# SparkFun_GPS_NEO_M9N.net
KiCad netlist of a schematic drawn in EAGLE
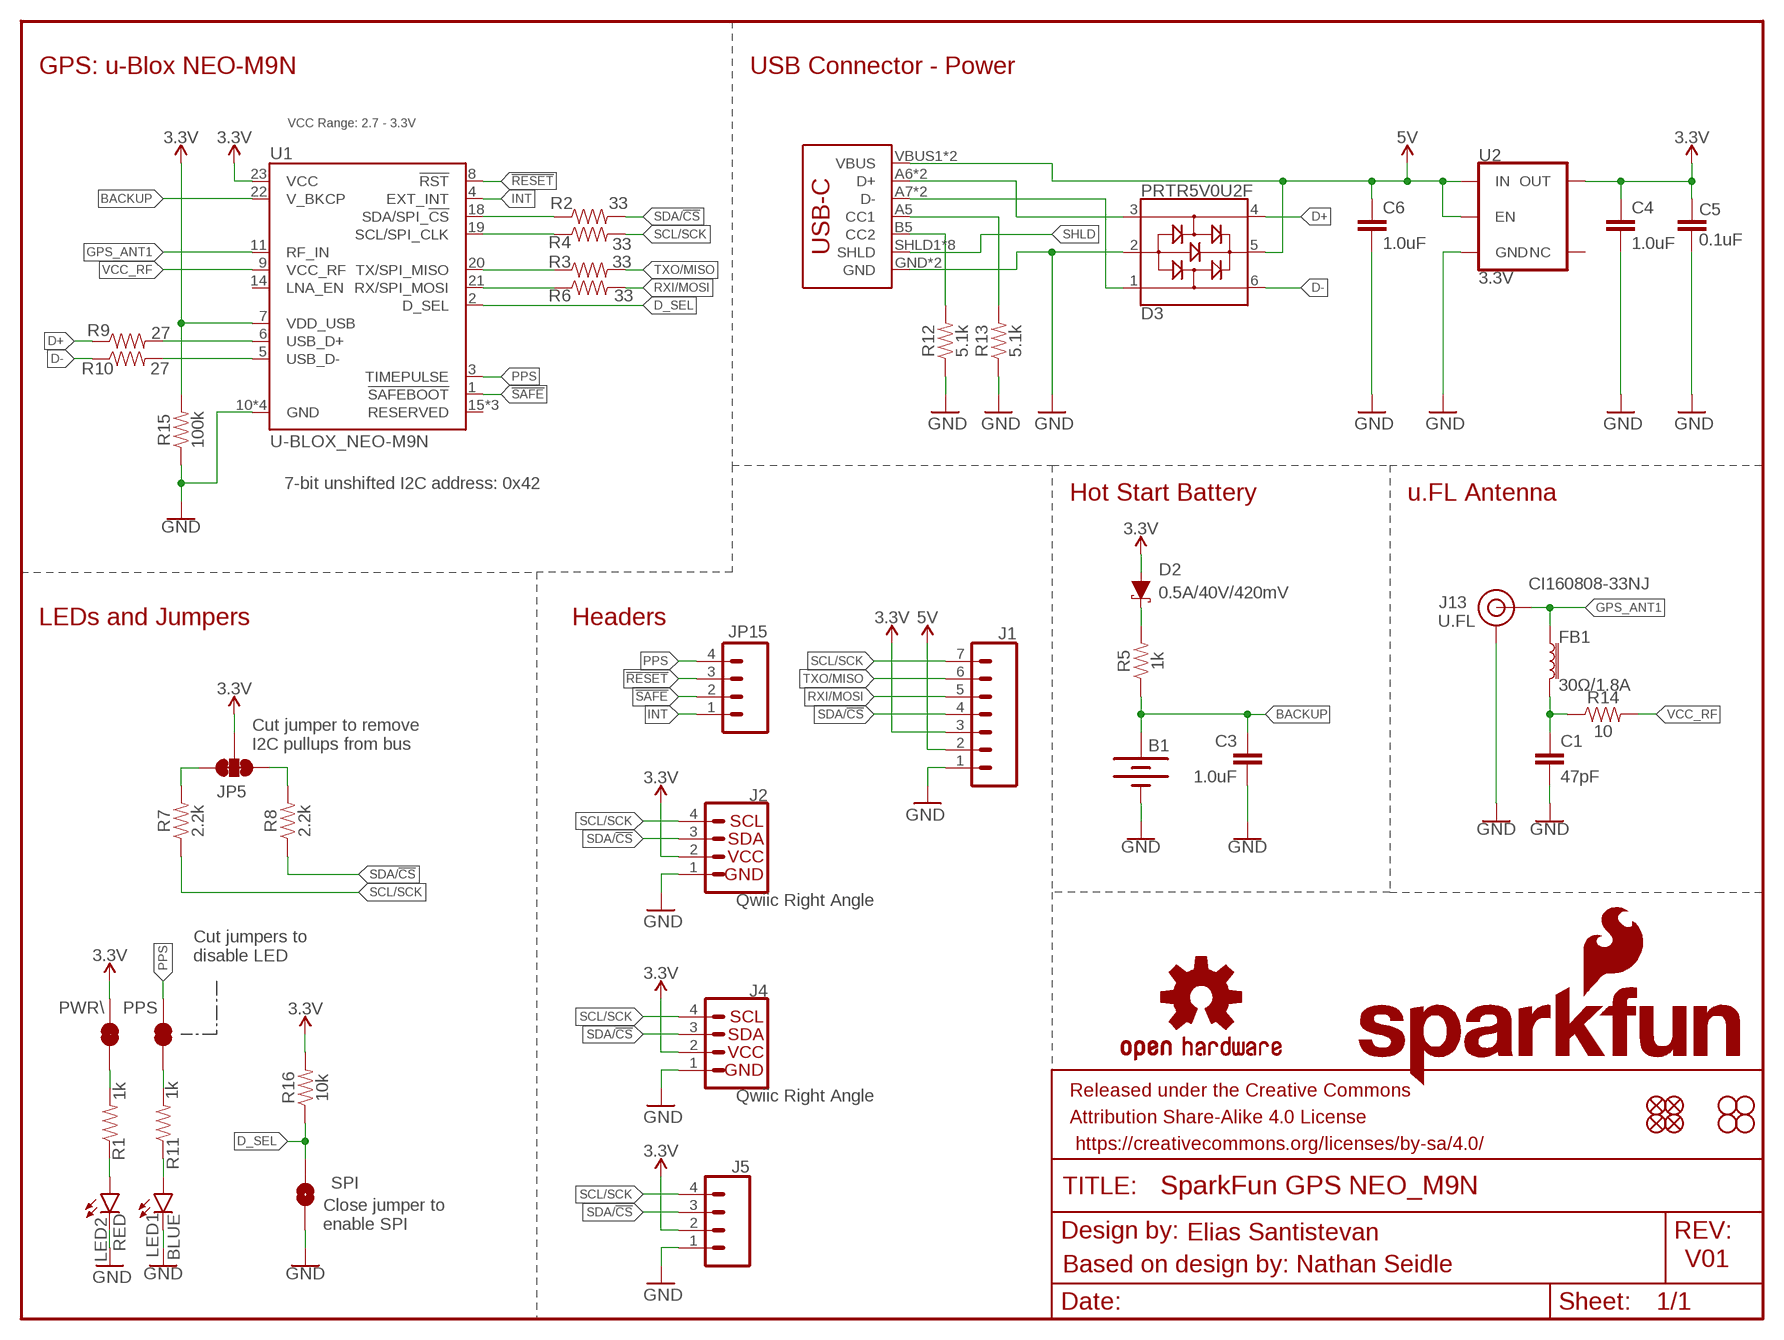
[diagram p0: schematic, sheet 1]

(export (version "E")
  (design (tool "Eeschema 10.0.6"))
  (components
    (comp (ref "B1")
      (value "6.8MM_COIN_CELL")
      (footprint "eagle-import:ML414H_IV01E")
      (libsource (lib "eagle-import") (part "ML414H_IV01E_BATTERY"))
    )
    (comp (ref "C1")
      (value "47pF")
      (footprint "eagle-import:0603")
      (libsource (lib "eagle-import") (part "47PF-0603-50V-5%"))
    )
    (comp (ref "C3")
      (value "1.0uF")
      (footprint "eagle-import:0603")
      (libsource (lib "eagle-import") (part "1.0UF-0603-16V-10%"))
    )
    (comp (ref "C4")
      (value "1.0uF")
      (footprint "eagle-import:0603")
      (libsource (lib "eagle-import") (part "1.0UF-0603-16V-10%"))
    )
    (comp (ref "C5")
      (value "0.1uF")
      (footprint "eagle-import:0603")
      (libsource (lib "eagle-import") (part "0.1UF-0603-25V-(+80/-20%)"))
    )
    (comp (ref "C6")
      (value "1.0uF")
      (footprint "eagle-import:0603")
      (libsource (lib "eagle-import") (part "1.0UF-0603-16V-10%"))
    )
    (comp (ref "D2")
      (value "0.5A/40V/420mV")
      (footprint "eagle-import:SOD-323")
      (libsource (lib "eagle-import") (part "DIODE-SCHOTTKY-PMEG4005EJ"))
    )
    (comp (ref "D3")
      (value "PRTR5V0U2F")
      (footprint "eagle-import:SOT886")
      (libsource (lib "eagle-import") (part "PRTR5V0U2F"))
    )
    (comp (ref "FB1")
      (value "30Ω/1.8A")
      (footprint "eagle-import:0603")
      (libsource (lib "eagle-import") (part "FERRITE_BEAD-0603"))
    )
    (comp (ref "FRAME1")
      (value "FRAME-LETTER")
      (footprint "eagle-import:CREATIVE_COMMONS")
      (libsource (lib "eagle-import") (part "FRAME-LETTER"))
    )
    (comp (ref "J1")
      (value "CONN_07NO_SILK")
      (footprint "eagle-import:1X07_NO_SILK")
      (libsource (lib "eagle-import") (part "CONN_07NO_SILK"))
    )
    (comp (ref "J2")
      (value "Qwiic Right Angle")
      (footprint "eagle-import:JST04_1MM_RA")
      (libsource (lib "eagle-import") (part "I2C_STANDARDQWIIC"))
    )
    (comp (ref "J3")
      (value "USB_C2-LAYER")
      (footprint "eagle-import:USB-C-16P")
      (libsource (lib "eagle-import") (part "USB_C2-LAYER"))
    )
    (comp (ref "J4")
      (value "Qwiic Right Angle")
      (footprint "eagle-import:JST04_1MM_RA")
      (libsource (lib "eagle-import") (part "I2C_STANDARDQWIIC"))
    )
    (comp (ref "J5")
      (value "CONN_041X04_NO_SILK")
      (footprint "eagle-import:1X04_NO_SILK")
      (libsource (lib "eagle-import") (part "CONN_041X04_NO_SILK"))
    )
    (comp (ref "J13")
      (value "U.FL")
      (footprint "eagle-import:U.FL")
      (libsource (lib "eagle-import") (part "U.FL2PIN"))
    )
    (comp (ref "JP5")
      (value "JUMPER-SMT_3_2-NC_TRACE_SILK")
      (footprint "eagle-import:SMT-JUMPER_3_2-NC_TRACE_SILK")
      (libsource (lib "eagle-import") (part "JUMPER-SMT_3_2-NC_TRACE_SILK"))
    )
    (comp (ref "JP15")
      (value "CONN_041X04_NO_SILK")
      (footprint "eagle-import:1X04_NO_SILK")
      (libsource (lib "eagle-import") (part "CONN_041X04_NO_SILK"))
    )
    (comp (ref "JP21")
      (value "FIDUCIALUFIDUCIAL")
      (footprint "eagle-import:MICRO-FIDUCIAL")
      (libsource (lib "eagle-import") (part "FIDUCIALUFIDUCIAL"))
    )
    (comp (ref "JP31")
      (value "STAND-OFF")
      (footprint "eagle-import:STAND-OFF")
      (libsource (lib "eagle-import") (part "STAND-OFF"))
    )
    (comp (ref "JP41")
      (value "STAND-OFF")
      (footprint "eagle-import:STAND-OFF")
      (libsource (lib "eagle-import") (part "STAND-OFF"))
    )
    (comp (ref "JP61")
      (value "FIDUCIALUFIDUCIAL")
      (footprint "eagle-import:MICRO-FIDUCIAL")
      (libsource (lib "eagle-import") (part "FIDUCIALUFIDUCIAL"))
    )
    (comp (ref "JP71")
      (value "FIDUCIALUFIDUCIAL")
      (footprint "eagle-import:MICRO-FIDUCIAL")
      (libsource (lib "eagle-import") (part "FIDUCIALUFIDUCIAL"))
    )
    (comp (ref "JP81")
      (value "FIDUCIALUFIDUCIAL")
      (footprint "eagle-import:MICRO-FIDUCIAL")
      (libsource (lib "eagle-import") (part "FIDUCIALUFIDUCIAL"))
    )
    (comp (ref "JP91")
      (value "STAND-OFF")
      (footprint "eagle-import:STAND-OFF")
      (libsource (lib "eagle-import") (part "STAND-OFF"))
    )
    (comp (ref "JP101")
      (value "STAND-OFF")
      (footprint "eagle-import:STAND-OFF")
      (libsource (lib "eagle-import") (part "STAND-OFF"))
    )
    (comp (ref "LED1")
      (value "BLUE")
      (footprint "eagle-import:LED-0603")
      (libsource (lib "eagle-import") (part "LED-BLUE0603"))
    )
    (comp (ref "LED2")
      (value "RED")
      (footprint "eagle-import:LED-0603")
      (libsource (lib "eagle-import") (part "LED-RED0603"))
    )
    (comp (ref "LOGO1")
      (value "OSHW-LOGOMINI")
      (footprint "eagle-import:OSHW-LOGO-MINI")
      (libsource (lib "eagle-import") (part "OSHW-LOGOMINI"))
    )
    (comp (ref "LOGO2")
      (value "SFE_LOGO_NAME_FLAME.1_INCH")
      (footprint "eagle-import:SFE_LOGO_NAME_FLAME_.1")
      (libsource (lib "eagle-import") (part "SFE_LOGO_NAME_FLAME.1_INCH"))
    )
    (comp (ref "PPS")
      (value "JUMPER-SMT_2_NC_TRACE_SILK")
      (footprint "eagle-import:SMT-JUMPER_2_NC_TRACE_SILK")
      (libsource (lib "eagle-import") (part "JUMPER-SMT_2_NC_TRACE_SILK"))
    )
    (comp (ref "PWR\\")
      (value "JUMPER-SMT_2_NC_TRACE_SILK")
      (footprint "eagle-import:SMT-JUMPER_2_NC_TRACE_SILK")
      (libsource (lib "eagle-import") (part "JUMPER-SMT_2_NC_TRACE_SILK"))
    )
    (comp (ref "R1")
      (value "1k")
      (footprint "eagle-import:0603")
      (libsource (lib "eagle-import") (part "1KOHM-0603-1/10W-1%"))
    )
    (comp (ref "R2")
      (value "33")
      (footprint "eagle-import:0603")
      (libsource (lib "eagle-import") (part "33OHM-0603-1/10W-1%"))
    )
    (comp (ref "R3")
      (value "33")
      (footprint "eagle-import:0603")
      (libsource (lib "eagle-import") (part "33OHM-0603-1/10W-1%"))
    )
    (comp (ref "R4")
      (value "33")
      (footprint "eagle-import:0603")
      (libsource (lib "eagle-import") (part "33OHM-0603-1/10W-1%"))
    )
    (comp (ref "R5")
      (value "1k")
      (footprint "eagle-import:0603")
      (libsource (lib "eagle-import") (part "1KOHM-0603-1/10W-1%"))
    )
    (comp (ref "R6")
      (value "33")
      (footprint "eagle-import:0603")
      (libsource (lib "eagle-import") (part "33OHM-0603-1/10W-1%"))
    )
    (comp (ref "R7")
      (value "2.2k")
      (footprint "eagle-import:0603")
      (libsource (lib "eagle-import") (part "2.2KOHM-0603-1/10W-1%"))
    )
    (comp (ref "R8")
      (value "2.2k")
      (footprint "eagle-import:0603")
      (libsource (lib "eagle-import") (part "2.2KOHM-0603-1/10W-1%"))
    )
    (comp (ref "R9")
      (value "27")
      (footprint "eagle-import:0603")
      (libsource (lib "eagle-import") (part "27OHM-0603-1/10W-1%"))
    )
    (comp (ref "R10")
      (value "27")
      (footprint "eagle-import:0603")
      (libsource (lib "eagle-import") (part "27OHM-0603-1/10W-1%"))
    )
    (comp (ref "R11")
      (value "1k")
      (footprint "eagle-import:0603")
      (libsource (lib "eagle-import") (part "1KOHM-0603-1/10W-1%"))
    )
    (comp (ref "R12")
      (value "5.1k")
      (footprint "eagle-import:0402")
      (libsource (lib "eagle-import") (part "5.1KOHM-0402-1/16W-1%"))
    )
    (comp (ref "R13")
      (value "5.1k")
      (footprint "eagle-import:0402")
      (libsource (lib "eagle-import") (part "5.1KOHM-0402-1/16W-1%"))
    )
    (comp (ref "R14")
      (value "10")
      (footprint "eagle-import:0603")
      (libsource (lib "eagle-import") (part "10OHM-0603-1/10W-1%"))
    )
    (comp (ref "R15")
      (value "100k")
      (footprint "eagle-import:0603")
      (libsource (lib "eagle-import") (part "100KOHM-0603-1/10W-1%"))
    )
    (comp (ref "R16")
      (value "10k")
      (footprint "eagle-import:0402")
      (libsource (lib "eagle-import") (part "10KOHM-0402-1/16W-1%"))
    )
    (comp (ref "SPI")
      (value "JUMPER-SMT_2_NO_SILK")
      (footprint "eagle-import:SMT-JUMPER_2_NO_SILK")
      (libsource (lib "eagle-import") (part "JUMPER-SMT_2_NO_SILK"))
    )
    (comp (ref "U1")
      (value "U-BLOX_NEO-M9N")
      (footprint "eagle-import:NEO-M9N")
      (libsource (lib "eagle-import") (part "U-BLOX_NEO-M9N"))
    )
    (comp (ref "U2")
      (value "3.3V")
      (footprint "eagle-import:SOT23-5")
      (libsource (lib "eagle-import") (part "V_REG_AP2112K-3.3V"))
    )
  )
  (nets
    (net (code "1") (name "/SDA{slash}~{CS}") (class "Default")
      (node (ref "J1") (pin "4") (pinfunction "4_4") (pintype "passive"))
      (node (ref "J2") (pin "3") (pinfunction "3_3") (pintype "passive"))
      (node (ref "J4") (pin "3") (pinfunction "3_3") (pintype "passive"))
      (node (ref "J5") (pin "3") (pinfunction "3_3") (pintype "passive"))
      (node (ref "R2") (pin "2") (pinfunction "2_2") (pintype "passive"))
      (node (ref "R8") (pin "1") (pinfunction "1_1") (pintype "passive"))
    )
    (net (code "2") (name "/~{RESET}") (class "Default")
      (node (ref "JP15") (pin "3") (pinfunction "3_3") (pintype "passive"))
      (node (ref "U1") (pin "8") (pinfunction "~{RST}_8") (pintype "bidirectional"))
    )
    (net (code "3") (name "/~{SAFE}") (class "Default")
      (node (ref "JP15") (pin "2") (pinfunction "2_2") (pintype "passive"))
      (node (ref "U1") (pin "1") (pinfunction "~{SAFEBOOT}_1") (pintype "bidirectional"))
    )
    (net (code "4") (name "3.3V") (class "Default")
      (node (ref "C4") (pin "1") (pinfunction "1_1") (pintype "passive"))
      (node (ref "C5") (pin "2") (pinfunction "2_2") (pintype "passive"))
      (node (ref "D2") (pin "A") (pinfunction "A_A") (pintype "passive"))
      (node (ref "J1") (pin "3") (pinfunction "3_3") (pintype "passive"))
      (node (ref "J2") (pin "2") (pinfunction "2_2") (pintype "power_in"))
      (node (ref "J4") (pin "2") (pinfunction "2_2") (pintype "power_in"))
      (node (ref "J5") (pin "2") (pinfunction "2_2") (pintype "passive"))
      (node (ref "JP5") (pin "2") (pinfunction "2_2") (pintype "passive"))
      (node (ref "PWR\\") (pin "2") (pinfunction "2_2") (pintype "passive"))
      (node (ref "R15") (pin "2") (pinfunction "2_2") (pintype "passive"))
      (node (ref "R16") (pin "2") (pinfunction "2_2") (pintype "passive"))
      (node (ref "U1") (pin "23") (pinfunction "VCC_23") (pintype "bidirectional"))
      (node (ref "U1") (pin "7") (pinfunction "VDD_USB_7") (pintype "bidirectional"))
      (node (ref "U2") (pin "5") (pinfunction "OUT_5") (pintype "passive"))
    )
    (net (code "5") (name "5V") (class "Default")
      (node (ref "C6") (pin "1") (pinfunction "1_1") (pintype "passive"))
      (node (ref "D3") (pin "5") (pinfunction "5_5") (pintype "bidirectional"))
      (node (ref "J1") (pin "2") (pinfunction "2_2") (pintype "passive"))
      (node (ref "J3") (pin "VBUS1") (pinfunction "VBUS_VBUS1") (pintype "bidirectional"))
      (node (ref "J3") (pin "VBUS2") (pinfunction "VBUS_VBUS2") (pintype "bidirectional"))
      (node (ref "U2") (pin "1") (pinfunction "IN_1") (pintype "input"))
      (node (ref "U2") (pin "3") (pinfunction "EN_3") (pintype "input"))
    )
    (net (code "6") (name "BACKUP") (class "Default")
      (node (ref "B1") (pin "+") (pinfunction "+_+") (pintype "power_in"))
      (node (ref "C3") (pin "1") (pinfunction "1_1") (pintype "passive"))
      (node (ref "R5") (pin "1") (pinfunction "1_1") (pintype "passive"))
      (node (ref "U1") (pin "22") (pinfunction "V_BKCP_22") (pintype "bidirectional"))
    )
    (net (code "7") (name "D+") (class "Default")
      (node (ref "D3") (pin "4") (pinfunction "4_4") (pintype "bidirectional"))
      (node (ref "R9") (pin "1") (pinfunction "1_1") (pintype "passive"))
    )
    (net (code "8") (name "D-") (class "Default")
      (node (ref "D3") (pin "6") (pinfunction "6_6") (pintype "bidirectional"))
      (node (ref "R10") (pin "1") (pinfunction "1_1") (pintype "passive"))
    )
    (net (code "9") (name "D_SEL") (class "Default")
      (node (ref "R16") (pin "1") (pinfunction "1_1") (pintype "passive"))
      (node (ref "SPI") (pin "2") (pinfunction "2_2") (pintype "passive"))
      (node (ref "U1") (pin "2") (pinfunction "D_SEL_2") (pintype "bidirectional"))
    )
    (net (code "10") (name "GND") (class "Default")
      (node (ref "B1") (pin "-") (pinfunction "-_-") (pintype "power_in"))
      (node (ref "C1") (pin "2") (pinfunction "2_2") (pintype "passive"))
      (node (ref "C3") (pin "2") (pinfunction "2_2") (pintype "passive"))
      (node (ref "C4") (pin "2") (pinfunction "2_2") (pintype "passive"))
      (node (ref "C5") (pin "1") (pinfunction "1_1") (pintype "passive"))
      (node (ref "C6") (pin "2") (pinfunction "2_2") (pintype "passive"))
      (node (ref "D3") (pin "2") (pinfunction "2_2") (pintype "bidirectional"))
      (node (ref "J1") (pin "1") (pinfunction "1_1") (pintype "passive"))
      (node (ref "J13") (pin "1") (pinfunction "GND_1") (pintype "bidirectional"))
      (node (ref "J13") (pin "2") (pinfunction "GND_2") (pintype "bidirectional"))
      (node (ref "J2") (pin "1") (pinfunction "1_1") (pintype "power_in"))
      (node (ref "J3") (pin "GND") (pinfunction "GND_GND") (pintype "bidirectional"))
      (node (ref "J3") (pin "GND2") (pinfunction "GND_GND2") (pintype "bidirectional"))
      (node (ref "J4") (pin "1") (pinfunction "1_1") (pintype "power_in"))
      (node (ref "J5") (pin "1") (pinfunction "1_1") (pintype "passive"))
      (node (ref "LED1") (pin "C") (pinfunction "C_C") (pintype "passive"))
      (node (ref "LED2") (pin "C") (pinfunction "C_C") (pintype "passive"))
      (node (ref "R12") (pin "1") (pinfunction "1_1") (pintype "passive"))
      (node (ref "R13") (pin "1") (pinfunction "1_1") (pintype "passive"))
      (node (ref "R15") (pin "1") (pinfunction "1_1") (pintype "passive"))
      (node (ref "SPI") (pin "1") (pinfunction "1_1") (pintype "passive"))
      (node (ref "U1") (pin "10") (pinfunction "GND_10") (pintype "bidirectional"))
      (node (ref "U1") (pin "12") (pinfunction "GND_12") (pintype "bidirectional"))
      (node (ref "U1") (pin "13") (pinfunction "GND_13") (pintype "bidirectional"))
      (node (ref "U1") (pin "24") (pinfunction "GND_24") (pintype "bidirectional"))
      (node (ref "U2") (pin "2") (pinfunction "GND_2") (pintype "input"))
    )
    (net (code "11") (name "GPS_ANT1") (class "Default")
      (node (ref "FB1") (pin "1") (pinfunction "1_1") (pintype "passive"))
      (node (ref "J13") (pin "FEED") (pinfunction "SIGNAL_FEED") (pintype "bidirectional"))
      (node (ref "U1") (pin "11") (pinfunction "RF_IN_11") (pintype "bidirectional"))
    )
    (net (code "12") (name "INT") (class "Default")
      (node (ref "JP15") (pin "1") (pinfunction "1_1") (pintype "passive"))
      (node (ref "U1") (pin "4") (pinfunction "EXT_INT_4") (pintype "bidirectional"))
    )
    (net (code "13") (name "Net-(C1-Pad1)") (class "Default")
      (node (ref "C1") (pin "1") (pinfunction "1_1") (pintype "passive"))
      (node (ref "FB1") (pin "2") (pinfunction "2_2") (pintype "passive"))
      (node (ref "R14") (pin "1") (pinfunction "1_1") (pintype "passive"))
    )
    (net (code "14") (name "Net-(D2-PadC)") (class "Default")
      (node (ref "D2") (pin "C") (pinfunction "C_C") (pintype "passive"))
      (node (ref "R5") (pin "2") (pinfunction "2_2") (pintype "passive"))
    )
    (net (code "15") (name "Net-(D3-Pad1)") (class "Default")
      (node (ref "D3") (pin "1") (pinfunction "1_1") (pintype "bidirectional"))
      (node (ref "J3") (pin "A7") (pinfunction "D-_A7") (pintype "bidirectional"))
      (node (ref "J3") (pin "B7") (pinfunction "D-_B7") (pintype "bidirectional"))
    )
    (net (code "16") (name "Net-(D3-Pad3)") (class "Default")
      (node (ref "D3") (pin "3") (pinfunction "3_3") (pintype "bidirectional"))
      (node (ref "J3") (pin "A6") (pinfunction "D+_A6") (pintype "bidirectional"))
      (node (ref "J3") (pin "B6") (pinfunction "D+_B6") (pintype "bidirectional"))
    )
    (net (code "17") (name "Net-(J3-CC1)") (class "Default")
      (node (ref "J3") (pin "A5") (pinfunction "CC1_A5") (pintype "bidirectional"))
      (node (ref "R13") (pin "2") (pinfunction "2_2") (pintype "passive"))
    )
    (net (code "18") (name "Net-(J3-CC2)") (class "Default")
      (node (ref "J3") (pin "B5") (pinfunction "CC2_B5") (pintype "bidirectional"))
      (node (ref "R12") (pin "2") (pinfunction "2_2") (pintype "passive"))
    )
    (net (code "19") (name "Net-(JP5-Pad1)") (class "Default")
      (node (ref "JP5") (pin "1") (pinfunction "1_1") (pintype "passive"))
      (node (ref "R8") (pin "2") (pinfunction "2_2") (pintype "passive"))
    )
    (net (code "20") (name "Net-(JP5-Pad3)") (class "Default")
      (node (ref "JP5") (pin "3") (pinfunction "3_3") (pintype "passive"))
      (node (ref "R7") (pin "2") (pinfunction "2_2") (pintype "passive"))
    )
    (net (code "21") (name "Net-(LED1-PadA)") (class "Default")
      (node (ref "LED1") (pin "A") (pinfunction "A_A") (pintype "passive"))
      (node (ref "R11") (pin "1") (pinfunction "1_1") (pintype "passive"))
    )
    (net (code "22") (name "Net-(LED2-PadA)") (class "Default")
      (node (ref "LED2") (pin "A") (pinfunction "A_A") (pintype "passive"))
      (node (ref "R1") (pin "1") (pinfunction "1_1") (pintype "passive"))
    )
    (net (code "23") (name "Net-(PPS-Pad1)") (class "Default")
      (node (ref "PPS") (pin "1") (pinfunction "1_1") (pintype "passive"))
      (node (ref "R11") (pin "2") (pinfunction "2_2") (pintype "passive"))
    )
    (net (code "24") (name "Net-(PWR\\-Pad1)") (class "Default")
      (node (ref "PWR\\") (pin "1") (pinfunction "1_1") (pintype "passive"))
      (node (ref "R1") (pin "2") (pinfunction "2_2") (pintype "passive"))
    )
    (net (code "25") (name "Net-(U1-RX{slash}SPI_MOSI)") (class "Default")
      (node (ref "R6") (pin "1") (pinfunction "1_1") (pintype "passive"))
      (node (ref "U1") (pin "21") (pinfunction "RX/SPI_MOSI_21") (pintype "bidirectional"))
    )
    (net (code "26") (name "Net-(U1-SCL{slash}SPI_CLK)") (class "Default")
      (node (ref "R4") (pin "1") (pinfunction "1_1") (pintype "passive"))
      (node (ref "U1") (pin "19") (pinfunction "SCL/SPI_CLK_19") (pintype "bidirectional"))
    )
    (net (code "27") (name "Net-(U1-SDA{slash}SPI_~{CS})") (class "Default")
      (node (ref "R2") (pin "1") (pinfunction "1_1") (pintype "passive"))
      (node (ref "U1") (pin "18") (pinfunction "SDA/SPI_~{CS}_18") (pintype "bidirectional"))
    )
    (net (code "28") (name "Net-(U1-TX{slash}SPI_MISO)") (class "Default")
      (node (ref "R3") (pin "1") (pinfunction "1_1") (pintype "passive"))
      (node (ref "U1") (pin "20") (pinfunction "TX/SPI_MISO_20") (pintype "bidirectional"))
    )
    (net (code "29") (name "Net-(U1-USB_D+)") (class "Default")
      (node (ref "R9") (pin "2") (pinfunction "2_2") (pintype "passive"))
      (node (ref "U1") (pin "6") (pinfunction "USB_D+_6") (pintype "bidirectional"))
    )
    (net (code "30") (name "Net-(U1-USB_D-)") (class "Default")
      (node (ref "R10") (pin "2") (pinfunction "2_2") (pintype "passive"))
      (node (ref "U1") (pin "5") (pinfunction "USB_D-_5") (pintype "bidirectional"))
    )
    (net (code "31") (name "PPS") (class "Default")
      (node (ref "JP15") (pin "4") (pinfunction "4_4") (pintype "passive"))
      (node (ref "PPS") (pin "2") (pinfunction "2_2") (pintype "passive"))
      (node (ref "U1") (pin "3") (pinfunction "TIMEPULSE_3") (pintype "bidirectional"))
    )
    (net (code "32") (name "RXI{slash}MOSI") (class "Default")
      (node (ref "J1") (pin "5") (pinfunction "5_5") (pintype "passive"))
      (node (ref "R6") (pin "2") (pinfunction "2_2") (pintype "passive"))
    )
    (net (code "33") (name "SCL{slash}SCK") (class "Default")
      (node (ref "J1") (pin "7") (pinfunction "7_7") (pintype "passive"))
      (node (ref "J2") (pin "4") (pinfunction "4_4") (pintype "passive"))
      (node (ref "J4") (pin "4") (pinfunction "4_4") (pintype "passive"))
      (node (ref "J5") (pin "4") (pinfunction "4_4") (pintype "passive"))
      (node (ref "R4") (pin "2") (pinfunction "2_2") (pintype "passive"))
      (node (ref "R7") (pin "1") (pinfunction "1_1") (pintype "passive"))
    )
    (net (code "34") (name "SHLD") (class "Default")
      (node (ref "J3") (pin "SHLD1") (pinfunction "SHLD_SHLD1") (pintype "bidirectional"))
      (node (ref "J3") (pin "SHLD2") (pinfunction "SHLD_SHLD2") (pintype "bidirectional"))
      (node (ref "J3") (pin "SHLD3") (pinfunction "SHLD_SHLD3") (pintype "bidirectional"))
      (node (ref "J3") (pin "SHLD4") (pinfunction "SHLD_SHLD4") (pintype "bidirectional"))
      (node (ref "J3") (pin "SHLD5") (pinfunction "SHLD_SHLD5") (pintype "bidirectional"))
      (node (ref "J3") (pin "SHLD6") (pinfunction "SHLD_SHLD6") (pintype "bidirectional"))
      (node (ref "J3") (pin "SHLD7") (pinfunction "SHLD_SHLD7") (pintype "bidirectional"))
      (node (ref "J3") (pin "SHLD8") (pinfunction "SHLD_SHLD8") (pintype "bidirectional"))
    )
    (net (code "35") (name "TXO{slash}MISO") (class "Default")
      (node (ref "J1") (pin "6") (pinfunction "6_6") (pintype "passive"))
      (node (ref "R3") (pin "2") (pinfunction "2_2") (pintype "passive"))
    )
    (net (code "36") (name "VCC_RF") (class "Default")
      (node (ref "R14") (pin "2") (pinfunction "2_2") (pintype "passive"))
      (node (ref "U1") (pin "9") (pinfunction "VCC_RF_9") (pintype "bidirectional"))
    )
    (net (code "37") (name "unconnected-(U1-LNA_EN-Pad14)") (class "Default")
      (node (ref "U1") (pin "14") (pinfunction "LNA_EN_14") (pintype "bidirectional"))
    )
    (net (code "38") (name "unconnected-(U1-RESERVED-Pad15)") (class "Default")
      (node (ref "U1") (pin "15") (pinfunction "RESERVED_15") (pintype "no_connect"))
    )
    (net (code "39") (name "unconnected-(U1-RESERVED-Pad16)") (class "Default")
      (node (ref "U1") (pin "16") (pinfunction "RESERVED_16") (pintype "no_connect"))
    )
    (net (code "40") (name "unconnected-(U1-RESERVED-Pad17)") (class "Default")
      (node (ref "U1") (pin "17") (pinfunction "RESERVED_17") (pintype "no_connect"))
    )
    (net (code "41") (name "unconnected-(U2-NC-Pad4)") (class "Default")
      (node (ref "U2") (pin "4") (pinfunction "NC_4") (pintype "no_connect"))
    )
  )
)
